# Top_Level.net
KiCad netlist of a schematic drawn in Altium Designer
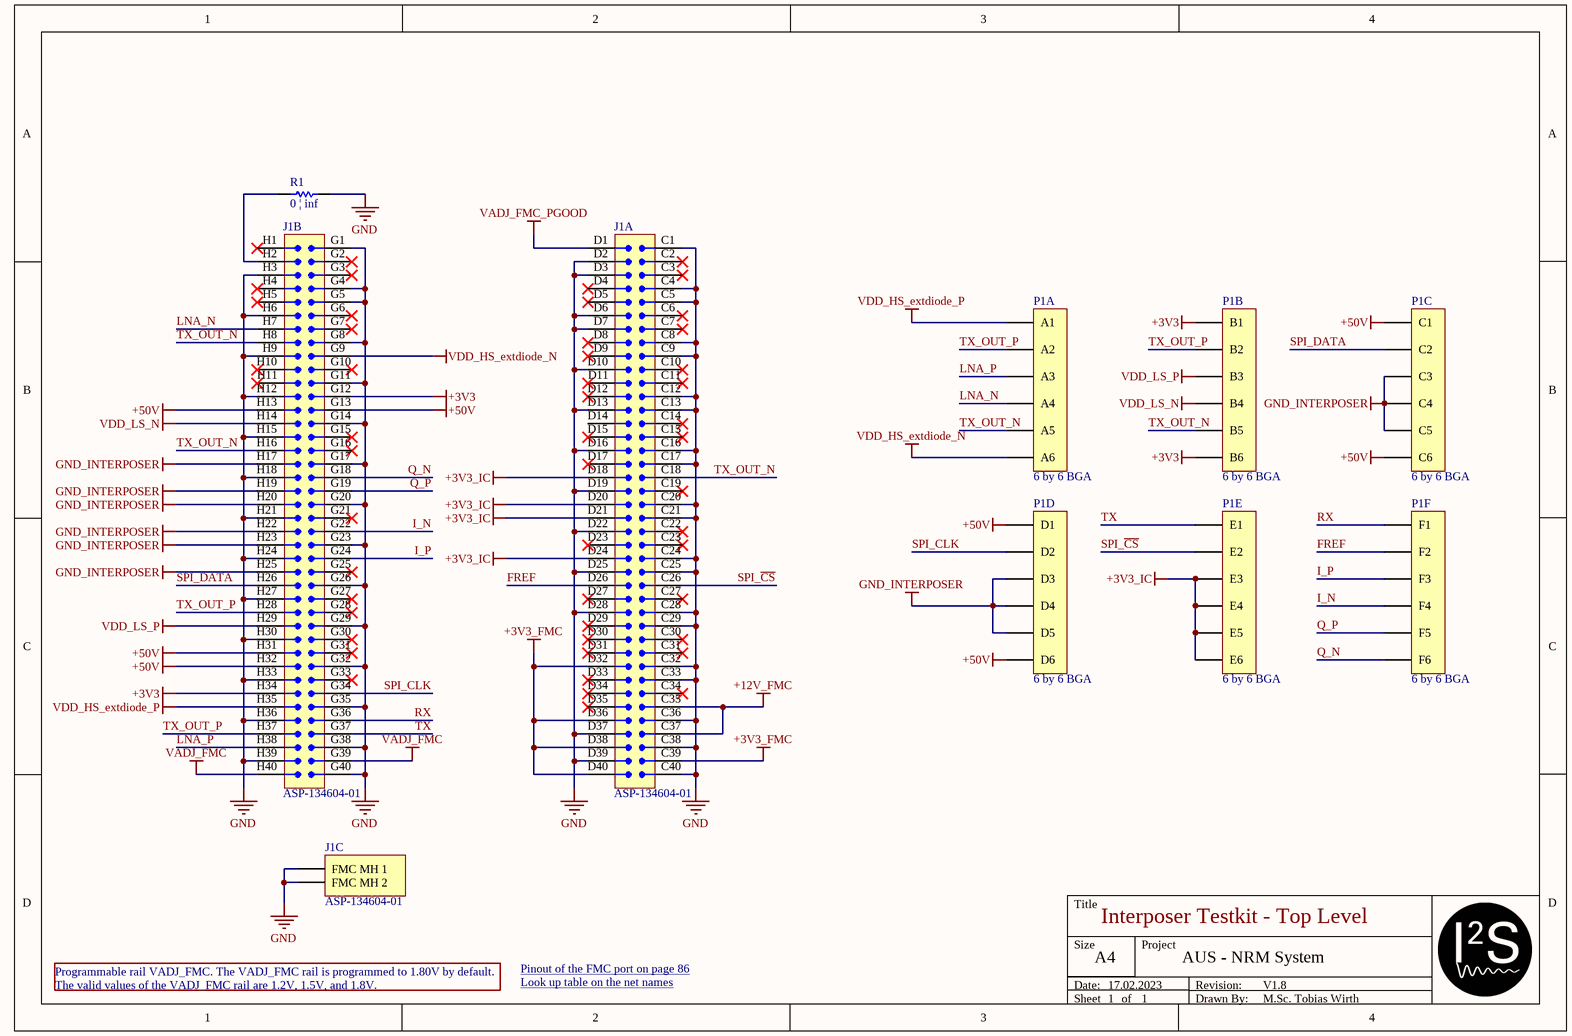
[diagram p0: Top_Level.SchDoc]

(export (version "E")
  (design (tool "Eeschema 10.0.6"))
  (components
    (comp (ref "J1")
      (value "ASP-134604-01")
      (footprint "ASP13460401")
      (description "Board to Board & FPGA Mezzanine Connector [LPC - \"ASP\"]")
      (libsource (lib "IIS-Lib_TW") (part "ASP-134604-01"))
    )
    (comp (ref "P1")
      (value "6 by 6 BGA")
      (footprint "BGA36C230P6X6_1500X1500X190 - Interposer")
      (libsource (lib "IIS-Lib_TW") (part "BGA_6x6"))
    )
    (comp (ref "R1") (value "0 ¦ inf") (footprint "RES_0603") (libsource (lib "IIS-Lib_TW") (part "Res")))
  )
  (nets
    (net (code "1") (name "+3V3") (class "Default")
      (node (ref "J1") (pin "G12") (pinfunction "G12_G12") (pintype "passive"))
      (node (ref "J1") (pin "H34") (pinfunction "H34_H34") (pintype "passive"))
      (node (ref "P1") (pin "B1") (pinfunction "B1_B1") (pintype "passive"))
      (node (ref "P1") (pin "B6") (pinfunction "B6_B6") (pintype "passive"))
    )
    (net (code "2") (name "+3V3_FMC") (class "Default")
      (node (ref "J1") (pin "C39") (pinfunction "C39_C39") (pintype "passive"))
      (node (ref "J1") (pin "D32") (pinfunction "D32_D32") (pintype "passive"))
      (node (ref "J1") (pin "D36") (pinfunction "D36_D36") (pintype "passive"))
      (node (ref "J1") (pin "D38") (pinfunction "D38_D38") (pintype "passive"))
      (node (ref "J1") (pin "D40") (pinfunction "D40_D40") (pintype "passive"))
    )
    (net (code "3") (name "+3V3_IC") (class "Default")
      (node (ref "J1") (pin "D18") (pinfunction "D18_D18") (pintype "passive"))
      (node (ref "J1") (pin "D20") (pinfunction "D20_D20") (pintype "passive"))
      (node (ref "J1") (pin "D21") (pinfunction "D21_D21") (pintype "passive"))
      (node (ref "J1") (pin "D24") (pinfunction "D24_D24") (pintype "passive"))
      (node (ref "P1") (pin "E3") (pinfunction "E3_E3") (pintype "passive"))
      (node (ref "P1") (pin "E4") (pinfunction "E4_E4") (pintype "passive"))
      (node (ref "P1") (pin "E5") (pinfunction "E5_E5") (pintype "passive"))
      (node (ref "P1") (pin "E6") (pinfunction "E6_E6") (pintype "passive"))
    )
    (net (code "4") (name "+12V_FMC") (class "Default")
      (node (ref "J1") (pin "C35") (pinfunction "C35_C35") (pintype "passive"))
      (node (ref "J1") (pin "C37") (pinfunction "C37_C37") (pintype "passive"))
    )
    (net (code "5") (name "+50V") (class "Default")
      (node (ref "J1") (pin "G13") (pinfunction "G13_G13") (pintype "passive"))
      (node (ref "J1") (pin "H13") (pinfunction "H13_H13") (pintype "passive"))
      (node (ref "J1") (pin "H31") (pinfunction "H31_H31") (pintype "passive"))
      (node (ref "J1") (pin "H32") (pinfunction "H32_H32") (pintype "passive"))
      (node (ref "P1") (pin "C1") (pinfunction "C1_C1") (pintype "passive"))
      (node (ref "P1") (pin "C6") (pinfunction "C6_C6") (pintype "passive"))
      (node (ref "P1") (pin "D1") (pinfunction "D1_D1") (pintype "passive"))
      (node (ref "P1") (pin "D6") (pinfunction "D6_D6") (pintype "passive"))
    )
    (net (code "6") (name "/FREF") (class "Default")
      (node (ref "J1") (pin "D26") (pinfunction "D26_D26") (pintype "passive"))
      (node (ref "P1") (pin "F2") (pinfunction "F2_F2") (pintype "passive"))
    )
    (net (code "7") (name "/I_N") (class "Default")
      (node (ref "J1") (pin "G22") (pinfunction "G22_G22") (pintype "passive"))
      (node (ref "P1") (pin "F4") (pinfunction "F4_F4") (pintype "passive"))
    )
    (net (code "8") (name "/I_P") (class "Default")
      (node (ref "J1") (pin "G24") (pinfunction "G24_G24") (pintype "passive"))
      (node (ref "P1") (pin "F3") (pinfunction "F3_F3") (pintype "passive"))
    )
    (net (code "9") (name "/LNA_N") (class "Default")
      (node (ref "J1") (pin "H7") (pinfunction "H7_H7") (pintype "passive"))
      (node (ref "P1") (pin "A4") (pinfunction "A4_A4") (pintype "passive"))
    )
    (net (code "10") (name "/LNA_P") (class "Default")
      (node (ref "J1") (pin "H38") (pinfunction "H38_H38") (pintype "passive"))
      (node (ref "P1") (pin "A3") (pinfunction "A3_A3") (pintype "passive"))
    )
    (net (code "11") (name "/Q_N") (class "Default")
      (node (ref "J1") (pin "G18") (pinfunction "G18_G18") (pintype "passive"))
      (node (ref "P1") (pin "F6") (pinfunction "F6_F6") (pintype "passive"))
    )
    (net (code "12") (name "/Q_P") (class "Default")
      (node (ref "J1") (pin "G19") (pinfunction "G19_G19") (pintype "passive"))
      (node (ref "P1") (pin "F5") (pinfunction "F5_F5") (pintype "passive"))
    )
    (net (code "13") (name "/RX") (class "Default")
      (node (ref "J1") (pin "G36") (pinfunction "G36_G36") (pintype "passive"))
      (node (ref "P1") (pin "F1") (pinfunction "F1_F1") (pintype "passive"))
    )
    (net (code "14") (name "/SPI_CLK") (class "Default")
      (node (ref "J1") (pin "G34") (pinfunction "G34_G34") (pintype "passive"))
      (node (ref "P1") (pin "D2") (pinfunction "D2_D2") (pintype "passive"))
    )
    (net (code "15") (name "/SPI_DATA") (class "Default")
      (node (ref "J1") (pin "H26") (pinfunction "H26_H26") (pintype "passive"))
      (node (ref "P1") (pin "C2") (pinfunction "C2_C2") (pintype "passive"))
    )
    (net (code "16") (name "/SPI_~{CS}") (class "Default")
      (node (ref "J1") (pin "C26") (pinfunction "C26_C26") (pintype "passive"))
      (node (ref "P1") (pin "E2") (pinfunction "E2_E2") (pintype "passive"))
    )
    (net (code "17") (name "/TX") (class "Default")
      (node (ref "J1") (pin "G37") (pinfunction "G37_G37") (pintype "passive"))
      (node (ref "P1") (pin "E1") (pinfunction "E1_E1") (pintype "passive"))
    )
    (net (code "18") (name "/TX_OUT_N") (class "Default")
      (node (ref "J1") (pin "C18") (pinfunction "C18_C18") (pintype "passive"))
      (node (ref "J1") (pin "H16") (pinfunction "H16_H16") (pintype "passive"))
      (node (ref "J1") (pin "H8") (pinfunction "H8_H8") (pintype "passive"))
      (node (ref "P1") (pin "A5") (pinfunction "A5_A5") (pintype "passive"))
      (node (ref "P1") (pin "B5") (pinfunction "B5_B5") (pintype "passive"))
    )
    (net (code "19") (name "/TX_OUT_P") (class "Default")
      (node (ref "J1") (pin "H28") (pinfunction "H28_H28") (pintype "passive"))
      (node (ref "J1") (pin "H37") (pinfunction "H37_H37") (pintype "passive"))
      (node (ref "P1") (pin "A2") (pinfunction "A2_A2") (pintype "passive"))
      (node (ref "P1") (pin "B2") (pinfunction "B2_B2") (pintype "passive"))
    )
    (net (code "20") (name "GND") (class "Default")
      (node (ref "J1") (pin "C1") (pinfunction "C1_C1") (pintype "passive"))
      (node (ref "J1") (pin "C12") (pinfunction "C12_C12") (pintype "passive"))
      (node (ref "J1") (pin "C13") (pinfunction "C13_C13") (pintype "passive"))
      (node (ref "J1") (pin "C16") (pinfunction "C16_C16") (pintype "passive"))
      (node (ref "J1") (pin "C17") (pinfunction "C17_C17") (pintype "passive"))
      (node (ref "J1") (pin "C20") (pinfunction "C20_C20") (pintype "passive"))
      (node (ref "J1") (pin "C21") (pinfunction "C21_C21") (pintype "passive"))
      (node (ref "J1") (pin "C24") (pinfunction "C24_C24") (pintype "passive"))
      (node (ref "J1") (pin "C25") (pinfunction "C25_C25") (pintype "passive"))
      (node (ref "J1") (pin "C28") (pinfunction "C28_C28") (pintype "passive"))
      (node (ref "J1") (pin "C29") (pinfunction "C29_C29") (pintype "passive"))
      (node (ref "J1") (pin "C32") (pinfunction "C32_C32") (pintype "passive"))
      (node (ref "J1") (pin "C33") (pinfunction "C33_C33") (pintype "passive"))
      (node (ref "J1") (pin "C36") (pinfunction "C36_C36") (pintype "passive"))
      (node (ref "J1") (pin "C38") (pinfunction "C38_C38") (pintype "passive"))
      (node (ref "J1") (pin "C4") (pinfunction "C4_C4") (pintype "passive"))
      (node (ref "J1") (pin "C40") (pinfunction "C40_C40") (pintype "passive"))
      (node (ref "J1") (pin "C5") (pinfunction "C5_C5") (pintype "passive"))
      (node (ref "J1") (pin "C8") (pinfunction "C8_C8") (pintype "passive"))
      (node (ref "J1") (pin "C9") (pinfunction "C9_C9") (pintype "passive"))
      (node (ref "J1") (pin "D10") (pinfunction "D10_D10") (pintype "passive"))
      (node (ref "J1") (pin "D13") (pinfunction "D13_D13") (pintype "passive"))
      (node (ref "J1") (pin "D16") (pinfunction "D16_D16") (pintype "passive"))
      (node (ref "J1") (pin "D19") (pinfunction "D19_D19") (pintype "passive"))
      (node (ref "J1") (pin "D2") (pinfunction "D2_D2") (pintype "passive"))
      (node (ref "J1") (pin "D22") (pinfunction "D22_D22") (pintype "passive"))
      (node (ref "J1") (pin "D25") (pinfunction "D25_D25") (pintype "passive"))
      (node (ref "J1") (pin "D28") (pinfunction "D28_D28") (pintype "passive"))
      (node (ref "J1") (pin "D3") (pinfunction "D3_D3") (pintype "passive"))
      (node (ref "J1") (pin "D37") (pinfunction "D37_D37") (pintype "passive"))
      (node (ref "J1") (pin "D39") (pinfunction "D39_D39") (pintype "passive"))
      (node (ref "J1") (pin "D6") (pinfunction "D6_D6") (pintype "passive"))
      (node (ref "J1") (pin "D7") (pinfunction "D7_D7") (pintype "passive"))
      (node (ref "J1") (pin "G1") (pinfunction "G1_G1") (pintype "passive"))
      (node (ref "J1") (pin "G11") (pinfunction "G11_G11") (pintype "passive"))
      (node (ref "J1") (pin "G14") (pinfunction "G14_G14") (pintype "passive"))
      (node (ref "J1") (pin "G17") (pinfunction "G17_G17") (pintype "passive"))
      (node (ref "J1") (pin "G20") (pinfunction "G20_G20") (pintype "passive"))
      (node (ref "J1") (pin "G23") (pinfunction "G23_G23") (pintype "passive"))
      (node (ref "J1") (pin "G26") (pinfunction "G26_G26") (pintype "passive"))
      (node (ref "J1") (pin "G29") (pinfunction "G29_G29") (pintype "passive"))
      (node (ref "J1") (pin "G32") (pinfunction "G32_G32") (pintype "passive"))
      (node (ref "J1") (pin "G35") (pinfunction "G35_G35") (pintype "passive"))
      (node (ref "J1") (pin "G38") (pinfunction "G38_G38") (pintype "passive"))
      (node (ref "J1") (pin "G4") (pinfunction "G4_G4") (pintype "passive"))
      (node (ref "J1") (pin "G40") (pinfunction "G40_G40") (pintype "passive"))
      (node (ref "J1") (pin "G5") (pinfunction "G5_G5") (pintype "passive"))
      (node (ref "J1") (pin "G8") (pinfunction "G8_G8") (pintype "passive"))
      (node (ref "J1") (pin "H12") (pinfunction "H12_H12") (pintype "passive"))
      (node (ref "J1") (pin "H15") (pinfunction "H15_H15") (pintype "passive"))
      (node (ref "J1") (pin "H18") (pinfunction "H18_H18") (pintype "passive"))
      (node (ref "J1") (pin "H21") (pinfunction "H21_H21") (pintype "passive"))
      (node (ref "J1") (pin "H24") (pinfunction "H24_H24") (pintype "passive"))
      (node (ref "J1") (pin "H27") (pinfunction "H27_H27") (pintype "passive"))
      (node (ref "J1") (pin "H3") (pinfunction "H3_H3") (pintype "passive"))
      (node (ref "J1") (pin "H30") (pinfunction "H30_H30") (pintype "passive"))
      (node (ref "J1") (pin "H33") (pinfunction "H33_H33") (pintype "passive"))
      (node (ref "J1") (pin "H36") (pinfunction "H36_H36") (pintype "passive"))
      (node (ref "J1") (pin "H39") (pinfunction "H39_H39") (pintype "passive"))
      (node (ref "J1") (pin "H6") (pinfunction "H6_H6") (pintype "passive"))
      (node (ref "J1") (pin "H9") (pinfunction "H9_H9") (pintype "passive"))
      (node (ref "J1") (pin "MH3") (pinfunction "FMC_MH_1_MH3") (pintype "passive"))
      (node (ref "J1") (pin "MH4") (pinfunction "FMC_MH_2_MH4") (pintype "passive"))
      (node (ref "R1") (pin "2") (pinfunction "2_2") (pintype "passive"))
    )
    (net (code "21") (name "GND_INTERPOSER") (class "Default")
      (node (ref "J1") (pin "H17") (pinfunction "H17_H17") (pintype "passive"))
      (node (ref "J1") (pin "H19") (pinfunction "H19_H19") (pintype "passive"))
      (node (ref "J1") (pin "H20") (pinfunction "H20_H20") (pintype "passive"))
      (node (ref "J1") (pin "H22") (pinfunction "H22_H22") (pintype "passive"))
      (node (ref "J1") (pin "H23") (pinfunction "H23_H23") (pintype "passive"))
      (node (ref "J1") (pin "H25") (pinfunction "H25_H25") (pintype "passive"))
      (node (ref "P1") (pin "C3") (pinfunction "C3_C3") (pintype "passive"))
      (node (ref "P1") (pin "C4") (pinfunction "C4_C4") (pintype "passive"))
      (node (ref "P1") (pin "C5") (pinfunction "C5_C5") (pintype "passive"))
      (node (ref "P1") (pin "D3") (pinfunction "D3_D3") (pintype "passive"))
      (node (ref "P1") (pin "D4") (pinfunction "D4_D4") (pintype "passive"))
      (node (ref "P1") (pin "D5") (pinfunction "D5_D5") (pintype "passive"))
    )
    (net (code "22") (name "Net-(J1-PadH2)") (class "Default")
      (node (ref "J1") (pin "H2") (pinfunction "H2_H2") (pintype "passive"))
      (node (ref "R1") (pin "1") (pinfunction "1_1") (pintype "passive"))
    )
    (net (code "23") (name "VADJ_FMC") (class "Default")
      (node (ref "J1") (pin "G39") (pinfunction "G39_G39") (pintype "passive"))
      (node (ref "J1") (pin "H40") (pinfunction "H40_H40") (pintype "passive"))
    )
    (net (code "24") (name "VADJ_FMC_PGOOD") (class "Default")
      (node (ref "J1") (pin "D1") (pinfunction "D1_D1") (pintype "passive"))
    )
    (net (code "25") (name "VDD_HS_extdiode_N") (class "Default")
      (node (ref "J1") (pin "G9") (pinfunction "G9_G9") (pintype "passive"))
      (node (ref "P1") (pin "A6") (pinfunction "A6_A6") (pintype "passive"))
    )
    (net (code "26") (name "VDD_HS_extdiode_P") (class "Default")
      (node (ref "J1") (pin "H35") (pinfunction "H35_H35") (pintype "passive"))
      (node (ref "P1") (pin "A1") (pinfunction "A1_A1") (pintype "passive"))
    )
    (net (code "27") (name "VDD_LS_N") (class "Default")
      (node (ref "J1") (pin "H14") (pinfunction "H14_H14") (pintype "passive"))
      (node (ref "P1") (pin "B4") (pinfunction "B4_B4") (pintype "passive"))
    )
    (net (code "28") (name "VDD_LS_P") (class "Default")
      (node (ref "J1") (pin "H29") (pinfunction "H29_H29") (pintype "passive"))
      (node (ref "P1") (pin "B3") (pinfunction "B3_B3") (pintype "passive"))
    )
    (net (code "29") (name "unconnected-(J1-PadC2)") (class "Default")
      (node (ref "J1") (pin "C2") (pinfunction "C2_C2") (pintype "passive+no_connect"))
    )
    (net (code "30") (name "unconnected-(J1-PadC3)") (class "Default")
      (node (ref "J1") (pin "C3") (pinfunction "C3_C3") (pintype "passive+no_connect"))
    )
    (net (code "31") (name "unconnected-(J1-PadC6)") (class "Default")
      (node (ref "J1") (pin "C6") (pinfunction "C6_C6") (pintype "passive+no_connect"))
    )
    (net (code "32") (name "unconnected-(J1-PadC7)") (class "Default")
      (node (ref "J1") (pin "C7") (pinfunction "C7_C7") (pintype "passive+no_connect"))
    )
    (net (code "33") (name "unconnected-(J1-PadC10)") (class "Default")
      (node (ref "J1") (pin "C10") (pinfunction "C10_C10") (pintype "passive+no_connect"))
    )
    (net (code "34") (name "unconnected-(J1-PadC11)") (class "Default")
      (node (ref "J1") (pin "C11") (pinfunction "C11_C11") (pintype "passive+no_connect"))
    )
    (net (code "35") (name "unconnected-(J1-PadC14)") (class "Default")
      (node (ref "J1") (pin "C14") (pinfunction "C14_C14") (pintype "passive+no_connect"))
    )
    (net (code "36") (name "unconnected-(J1-PadC15)") (class "Default")
      (node (ref "J1") (pin "C15") (pinfunction "C15_C15") (pintype "passive+no_connect"))
    )
    (net (code "37") (name "unconnected-(J1-PadC19)") (class "Default")
      (node (ref "J1") (pin "C19") (pinfunction "C19_C19") (pintype "passive+no_connect"))
    )
    (net (code "38") (name "unconnected-(J1-PadC22)") (class "Default")
      (node (ref "J1") (pin "C22") (pinfunction "C22_C22") (pintype "passive+no_connect"))
    )
    (net (code "39") (name "unconnected-(J1-PadC23)") (class "Default")
      (node (ref "J1") (pin "C23") (pinfunction "C23_C23") (pintype "passive+no_connect"))
    )
    (net (code "40") (name "unconnected-(J1-PadC27)") (class "Default")
      (node (ref "J1") (pin "C27") (pinfunction "C27_C27") (pintype "passive+no_connect"))
    )
    (net (code "41") (name "unconnected-(J1-PadC30)") (class "Default")
      (node (ref "J1") (pin "C30") (pinfunction "C30_C30") (pintype "passive+no_connect"))
    )
    (net (code "42") (name "unconnected-(J1-PadC31)") (class "Default")
      (node (ref "J1") (pin "C31") (pinfunction "C31_C31") (pintype "passive+no_connect"))
    )
    (net (code "43") (name "unconnected-(J1-PadC34)") (class "Default")
      (node (ref "J1") (pin "C34") (pinfunction "C34_C34") (pintype "passive+no_connect"))
    )
    (net (code "44") (name "unconnected-(J1-PadD4)") (class "Default")
      (node (ref "J1") (pin "D4") (pinfunction "D4_D4") (pintype "passive+no_connect"))
    )
    (net (code "45") (name "unconnected-(J1-PadD5)") (class "Default")
      (node (ref "J1") (pin "D5") (pinfunction "D5_D5") (pintype "passive+no_connect"))
    )
    (net (code "46") (name "unconnected-(J1-PadD8)") (class "Default")
      (node (ref "J1") (pin "D8") (pinfunction "D8_D8") (pintype "passive+no_connect"))
    )
    (net (code "47") (name "unconnected-(J1-PadD9)") (class "Default")
      (node (ref "J1") (pin "D9") (pinfunction "D9_D9") (pintype "passive+no_connect"))
    )
    (net (code "48") (name "unconnected-(J1-PadD11)") (class "Default")
      (node (ref "J1") (pin "D11") (pinfunction "D11_D11") (pintype "passive+no_connect"))
    )
    (net (code "49") (name "unconnected-(J1-PadD12)") (class "Default")
      (node (ref "J1") (pin "D12") (pinfunction "D12_D12") (pintype "passive+no_connect"))
    )
    (net (code "50") (name "unconnected-(J1-PadD14)") (class "Default")
      (node (ref "J1") (pin "D14") (pinfunction "D14_D14") (pintype "passive"))
    )
    (net (code "51") (name "unconnected-(J1-PadD15)") (class "Default")
      (node (ref "J1") (pin "D15") (pinfunction "D15_D15") (pintype "passive+no_connect"))
    )
    (net (code "52") (name "unconnected-(J1-PadD17)") (class "Default")
      (node (ref "J1") (pin "D17") (pinfunction "D17_D17") (pintype "passive+no_connect"))
    )
    (net (code "53") (name "unconnected-(J1-PadD23)") (class "Default")
      (node (ref "J1") (pin "D23") (pinfunction "D23_D23") (pintype "passive+no_connect"))
    )
    (net (code "54") (name "unconnected-(J1-PadD27)") (class "Default")
      (node (ref "J1") (pin "D27") (pinfunction "D27_D27") (pintype "passive+no_connect"))
    )
    (net (code "55") (name "unconnected-(J1-PadD29)") (class "Default")
      (node (ref "J1") (pin "D29") (pinfunction "D29_D29") (pintype "passive+no_connect"))
    )
    (net (code "56") (name "unconnected-(J1-PadD30)") (class "Default")
      (node (ref "J1") (pin "D30") (pinfunction "D30_D30") (pintype "passive+no_connect"))
    )
    (net (code "57") (name "unconnected-(J1-PadD31)") (class "Default")
      (node (ref "J1") (pin "D31") (pinfunction "D31_D31") (pintype "passive+no_connect"))
    )
    (net (code "58") (name "unconnected-(J1-PadD33)") (class "Default")
      (node (ref "J1") (pin "D33") (pinfunction "D33_D33") (pintype "passive+no_connect"))
    )
    (net (code "59") (name "unconnected-(J1-PadD34)") (class "Default")
      (node (ref "J1") (pin "D34") (pinfunction "D34_D34") (pintype "passive+no_connect"))
    )
    (net (code "60") (name "unconnected-(J1-PadD35)") (class "Default")
      (node (ref "J1") (pin "D35") (pinfunction "D35_D35") (pintype "passive+no_connect"))
    )
    (net (code "61") (name "unconnected-(J1-PadG2)") (class "Default")
      (node (ref "J1") (pin "G2") (pinfunction "G2_G2") (pintype "passive+no_connect"))
    )
    (net (code "62") (name "unconnected-(J1-PadG3)") (class "Default")
      (node (ref "J1") (pin "G3") (pinfunction "G3_G3") (pintype "passive+no_connect"))
    )
    (net (code "63") (name "unconnected-(J1-PadG6)") (class "Default")
      (node (ref "J1") (pin "G6") (pinfunction "G6_G6") (pintype "passive+no_connect"))
    )
    (net (code "64") (name "unconnected-(J1-PadG7)") (class "Default")
      (node (ref "J1") (pin "G7") (pinfunction "G7_G7") (pintype "passive+no_connect"))
    )
    (net (code "65") (name "unconnected-(J1-PadG10)") (class "Default")
      (node (ref "J1") (pin "G10") (pinfunction "G10_G10") (pintype "passive+no_connect"))
    )
    (net (code "66") (name "unconnected-(J1-PadG15)") (class "Default")
      (node (ref "J1") (pin "G15") (pinfunction "G15_G15") (pintype "passive+no_connect"))
    )
    (net (code "67") (name "unconnected-(J1-PadG16)") (class "Default")
      (node (ref "J1") (pin "G16") (pinfunction "G16_G16") (pintype "passive+no_connect"))
    )
    (net (code "68") (name "unconnected-(J1-PadG21)") (class "Default")
      (node (ref "J1") (pin "G21") (pinfunction "G21_G21") (pintype "passive+no_connect"))
    )
    (net (code "69") (name "unconnected-(J1-PadG25)") (class "Default")
      (node (ref "J1") (pin "G25") (pinfunction "G25_G25") (pintype "passive+no_connect"))
    )
    (net (code "70") (name "unconnected-(J1-PadG27)") (class "Default")
      (node (ref "J1") (pin "G27") (pinfunction "G27_G27") (pintype "passive+no_connect"))
    )
    (net (code "71") (name "unconnected-(J1-PadG28)") (class "Default")
      (node (ref "J1") (pin "G28") (pinfunction "G28_G28") (pintype "passive+no_connect"))
    )
    (net (code "72") (name "unconnected-(J1-PadG30)") (class "Default")
      (node (ref "J1") (pin "G30") (pinfunction "G30_G30") (pintype "passive+no_connect"))
    )
    (net (code "73") (name "unconnected-(J1-PadG31)") (class "Default")
      (node (ref "J1") (pin "G31") (pinfunction "G31_G31") (pintype "passive+no_connect"))
    )
    (net (code "74") (name "unconnected-(J1-PadG33)") (class "Default")
      (node (ref "J1") (pin "G33") (pinfunction "G33_G33") (pintype "passive+no_connect"))
    )
    (net (code "75") (name "unconnected-(J1-PadH1)") (class "Default")
      (node (ref "J1") (pin "H1") (pinfunction "H1_H1") (pintype "passive+no_connect"))
    )
    (net (code "76") (name "unconnected-(J1-PadH4)") (class "Default")
      (node (ref "J1") (pin "H4") (pinfunction "H4_H4") (pintype "passive+no_connect"))
    )
    (net (code "77") (name "unconnected-(J1-PadH5)") (class "Default")
      (node (ref "J1") (pin "H5") (pinfunction "H5_H5") (pintype "passive+no_connect"))
    )
    (net (code "78") (name "unconnected-(J1-PadH10)") (class "Default")
      (node (ref "J1") (pin "H10") (pinfunction "H10_H10") (pintype "passive+no_connect"))
    )
    (net (code "79") (name "unconnected-(J1-PadH11)") (class "Default")
      (node (ref "J1") (pin "H11") (pinfunction "H11_H11") (pintype "passive+no_connect"))
    )
  )
)
